# microcontrollerOptical.net
KiCad netlist of a schematic drawn in Altium Designer
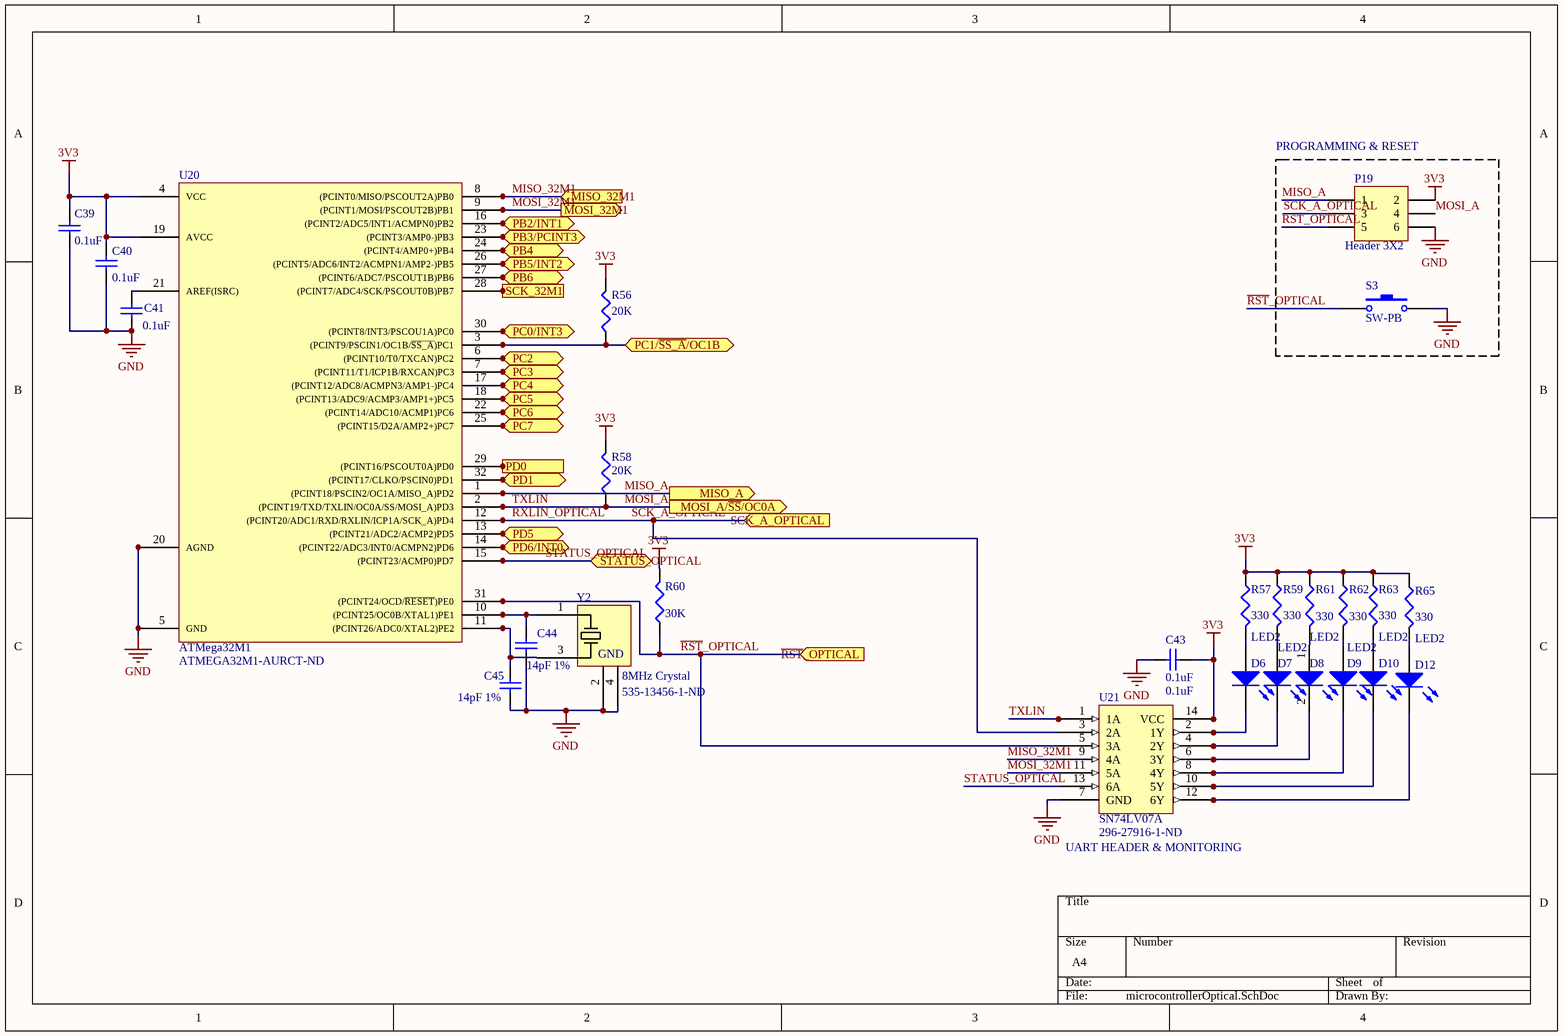
[diagram p0: microcontrollerOptical.SchDoc]

(export (version "E")
  (design (tool "Eeschema 10.0.6"))
  (components
    (comp (ref "C39")
      (value "0.1uF")
      (footprint "1608[0603]")
      (description "Capacitor (Semiconductor SIM Model)")
      (fields (field (name "PUBLISHER") "Altium Limited"))
      (libsource (lib "Miscellaneous Devices") (part "Cap Semi"))
    )
    (comp (ref "C40")
      (value "0.1uF")
      (footprint "1608[0603]")
      (description "Capacitor (Semiconductor SIM Model)")
      (fields (field (name "PUBLISHER") "Altium Limited"))
      (libsource (lib "Miscellaneous Devices") (part "Cap Semi"))
    )
    (comp (ref "C41")
      (value "0.1uF")
      (footprint "1608[0603]")
      (description "Capacitor (Semiconductor SIM Model)")
      (fields (field (name "PUBLISHER") "Altium Limited"))
      (libsource (lib "Miscellaneous Devices") (part "Cap Semi"))
    )
    (comp (ref "C43")
      (value "0.1uF")
      (footprint "1608[0603]")
      (description "Capacitor (Semiconductor SIM Model)")
      (fields (field (name "ALTIUM_VALUE") "0.1uF") (field (name "PUBLISHER") "Altium Limited"))
      (libsource (lib "Miscellaneous Devices") (part "Cap Semi"))
    )
    (comp (ref "C44")
      (value "14pF 1%")
      (footprint "1608[0603]")
      (description "Capacitor (Semiconductor SIM Model)")
      (fields (field (name "Comment") "15pF 1%") (field (name "PUBLISHER") "Altium Limited"))
      (libsource (lib "Miscellaneous Devices") (part "Cap Semi"))
    )
    (comp (ref "C45")
      (value "14pF 1%")
      (footprint "1608[0603]")
      (description "Capacitor (Semiconductor SIM Model)")
      (fields (field (name "Comment") "15pF 1%") (field (name "PUBLISHER") "Altium Limited"))
      (libsource (lib "Miscellaneous Devices") (part "Cap Semi"))
    )
    (comp (ref "D6")
      (value "LED2")
      (footprint "0603-LED")
      (description "Typical RED, GREEN, YELLOW, AMBER GaAs LED")
      (fields (field (name "PUBLISHER") "Altium Limited"))
      (libsource (lib "Miscellaneous Devices") (part "LED2"))
    )
    (comp (ref "D7")
      (value "LED2")
      (footprint "0603-LED")
      (description "Typical RED, GREEN, YELLOW, AMBER GaAs LED")
      (fields (field (name "PUBLISHER") "Altium Limited"))
      (libsource (lib "Miscellaneous Devices") (part "LED2"))
    )
    (comp (ref "D8")
      (value "LED2")
      (footprint "0603-LED")
      (description "Typical RED, GREEN, YELLOW, AMBER GaAs LED")
      (fields (field (name "PUBLISHER") "Altium Limited"))
      (libsource (lib "") (part "LED2_1"))
    )
    (comp (ref "D9")
      (value "LED2")
      (footprint "0603-LED")
      (description "Typical RED, GREEN, YELLOW, AMBER GaAs LED")
      (fields (field (name "PUBLISHER") "Altium Limited"))
      (libsource (lib "Miscellaneous Devices") (part "LED2"))
    )
    (comp (ref "D10")
      (value "LED2")
      (footprint "0603-LED")
      (description "Typical RED, GREEN, YELLOW, AMBER GaAs LED")
      (fields (field (name "PUBLISHER") "Altium Limited"))
      (libsource (lib "Miscellaneous Devices") (part "LED2"))
    )
    (comp (ref "D12")
      (value "LED2")
      (footprint "0603-LED")
      (description "Typical RED, GREEN, YELLOW, AMBER GaAs LED")
      (fields (field (name "PUBLISHER") "Altium Limited"))
      (libsource (lib "Miscellaneous Devices") (part "LED2"))
    )
    (comp (ref "P19")
      (value "Header 3X2")
      (footprint "HDR2X3")
      (description "Header, 3-Pin, Dual row")
      (fields (field (name "PUBLISHER") "Altium Limited"))
      (libsource (lib "Miscellaneous Connectors") (part "Header 3X2"))
    )
    (comp (ref "R56")
      (value "20K")
      (footprint "J1-0603")
      (description "Resistor")
      (fields (field (name "PUBLISHER") "Altium Limited"))
      (libsource (lib "Miscellaneous Devices") (part "Res3"))
    )
    (comp (ref "R57")
      (value "330")
      (footprint "J1-0603")
      (description "Resistor")
      (fields (field (name "PUBLISHER") "Altium Limited"))
      (libsource (lib "Miscellaneous Devices") (part "Res3"))
    )
    (comp (ref "R58")
      (value "20K")
      (footprint "J1-0603")
      (description "Resistor")
      (fields (field (name "PUBLISHER") "Altium Limited"))
      (libsource (lib "Miscellaneous Devices") (part "Res3"))
    )
    (comp (ref "R59")
      (value "330")
      (footprint "J1-0603")
      (description "Resistor")
      (fields (field (name "PUBLISHER") "Altium Limited"))
      (libsource (lib "Miscellaneous Devices") (part "Res3"))
    )
    (comp (ref "R60")
      (value "30K")
      (footprint "J1-0603")
      (description "Resistor")
      (fields (field (name "PUBLISHER") "Altium Limited"))
      (libsource (lib "Miscellaneous Devices") (part "Res3"))
    )
    (comp (ref "R61")
      (value "330")
      (footprint "J1-0603")
      (description "Resistor")
      (fields (field (name "PUBLISHER") "Altium Limited"))
      (libsource (lib "Miscellaneous Devices") (part "Res3"))
    )
    (comp (ref "R62")
      (value "330")
      (footprint "J1-0603")
      (description "Resistor")
      (fields (field (name "PUBLISHER") "Altium Limited"))
      (libsource (lib "Miscellaneous Devices") (part "Res3"))
    )
    (comp (ref "R63")
      (value "330")
      (footprint "J1-0603")
      (description "Resistor")
      (fields (field (name "PUBLISHER") "Altium Limited"))
      (libsource (lib "Miscellaneous Devices") (part "Res3"))
    )
    (comp (ref "R65")
      (value "330")
      (footprint "J1-0603")
      (description "Resistor")
      (fields (field (name "PUBLISHER") "Altium Limited"))
      (libsource (lib "Miscellaneous Devices") (part "Res3"))
    )
    (comp (ref "S3")
      (value "SW-PB")
      (footprint "Pushbutton")
      (description "Switch")
      (fields (field (name "PUBLISHER") "Altium Limited"))
      (libsource (lib "Miscellaneous Devices") (part "SW-PB"))
    )
    (comp (ref "U20")
      (value "ATMega32M1")
      (footprint "QFP80P900X900X120-32N")
      (description "Atmel 8-bit AVR microcontroller.")
      (fields (field (name "SUPPLIER PART NUMBER 1") "ATMEGA32M1-AURCT-ND"))
      (libsource (lib "ICs") (part "ATMega32M1"))
    )
    (comp (ref "U21")
      (value "SN74LV07A")
      (footprint "SOP65P640X120-14N")
      (description "Six element 1-bit non-inverting open-drain buffer.")
      (fields (field (name "SUPPLIER PART NUMBER") "296-27916-1-ND"))
      (libsource (lib "ICs") (part "SN74LV07A"))
    )
    (comp (ref "Y2")
      (value "8MHz Crystal")
      (footprint "OSCSC500X320X110-4N")
      (description "8MHz Abracom 4-pin crystal.")
      (fields (field (name "SUPPLIER PART NUMBER 1") "535-13456-1-ND"))
      (libsource (lib "ICs") (part "8MHz Abracom 4-Pin Crystal"))
    )
  )
  (nets
    (net (code "1") (name "/MISO_32M1") (class "Default")
      (node (ref "U20") (pin "8") (pinfunction "(PCINT0/MISO/PSCOUT2A)PB0_8") (pintype "passive"))
      (node (ref "U21") (pin "9") (pinfunction "4A_9") (pintype "input"))
    )
    (net (code "2") (name "/MISO_A") (class "Default")
      (node (ref "P19") (pin "1") (pinfunction "1_1") (pintype "passive"))
      (node (ref "U20") (pin "1") (pinfunction "(PCINT18/PSCIN2/OC1A/MISO_A)PD2_1") (pintype "passive"))
    )
    (net (code "3") (name "/MOSI_32M1") (class "Default")
      (node (ref "U20") (pin "9") (pinfunction "(PCINT1/MOSI/PSCOUT2B)PB1_9") (pintype "passive"))
      (node (ref "U21") (pin "11") (pinfunction "5A_11") (pintype "input"))
    )
    (net (code "4") (name "/MOSI_A") (class "Default")
      (node (ref "P19") (pin "4") (pinfunction "4_4") (pintype "passive"))
      (node (ref "R58") (pin "1") (pinfunction "1_1") (pintype "passive"))
      (node (ref "U20") (pin "2") (pinfunction "(PCINT19/TXD/TXLIN/OC0A/SS/MOSI_A)PD3_2") (pintype "passive"))
      (node (ref "U21") (pin "1") (pinfunction "1A_1") (pintype "input"))
    )
    (net (code "5") (name "/PB2{slash}INT1") (class "Default")
      (node (ref "U20") (pin "16") (pinfunction "(PCINT2/ADC5/INT1/ACMPN0)PB2_16") (pintype "passive"))
    )
    (net (code "6") (name "/PB3{slash}PCINT3") (class "Default")
      (node (ref "U20") (pin "23") (pinfunction "(PCINT3/AMP0-)PB3_23") (pintype "passive"))
    )
    (net (code "7") (name "/PB4") (class "Default")
      (node (ref "U20") (pin "24") (pinfunction "(PCINT4/AMP0+)PB4_24") (pintype "passive"))
    )
    (net (code "8") (name "/PB5{slash}INT2") (class "Default")
      (node (ref "U20") (pin "26") (pinfunction "(PCINT5/ADC6/INT2/ACMPN1/AMP2-)PB5_26") (pintype "passive"))
    )
    (net (code "9") (name "/PB6") (class "Default")
      (node (ref "U20") (pin "27") (pinfunction "(PCINT6/ADC7/PSCOUT1B)PB6_27") (pintype "passive"))
    )
    (net (code "10") (name "/PC0{slash}INT3") (class "Default")
      (node (ref "U20") (pin "30") (pinfunction "(PCINT8/INT3/PSCOU1A)PC0_30") (pintype "passive"))
    )
    (net (code "11") (name "/PC1{slash}~{SS_A}{slash}OC1B") (class "Default")
      (node (ref "R56") (pin "1") (pinfunction "1_1") (pintype "passive"))
      (node (ref "U20") (pin "3") (pinfunction "(PCINT9/PSCIN1/OC1B/~{SS_A})PC1_3") (pintype "passive"))
    )
    (net (code "12") (name "/PC2") (class "Default")
      (node (ref "U20") (pin "6") (pinfunction "(PCINT10/T0/TXCAN)PC2_6") (pintype "passive"))
    )
    (net (code "13") (name "/PC3") (class "Default")
      (node (ref "U20") (pin "7") (pinfunction "(PCINT11/T1/ICP1B/RXCAN)PC3_7") (pintype "passive"))
    )
    (net (code "14") (name "/PC4") (class "Default")
      (node (ref "U20") (pin "17") (pinfunction "(PCINT12/ADC8/ACMPN3/AMP1-)PC4_17") (pintype "passive"))
    )
    (net (code "15") (name "/PC5") (class "Default")
      (node (ref "U20") (pin "18") (pinfunction "(PCINT13/ADC9/ACMP3/AMP1+)PC5_18") (pintype "passive"))
    )
    (net (code "16") (name "/PC6") (class "Default")
      (node (ref "U20") (pin "22") (pinfunction "(PCINT14/ADC10/ACMP1)PC6_22") (pintype "passive"))
    )
    (net (code "17") (name "/PC7") (class "Default")
      (node (ref "U20") (pin "25") (pinfunction "(PCINT15/D2A/AMP2+)PC7_25") (pintype "passive"))
    )
    (net (code "18") (name "/PD0") (class "Default")
      (node (ref "U20") (pin "29") (pinfunction "(PCINT16/PSCOUT0A)PD0_29") (pintype "passive"))
    )
    (net (code "19") (name "/PD1") (class "Default")
      (node (ref "U20") (pin "32") (pinfunction "(PCINT17/CLKO/PSCIN0)PD1_32") (pintype "passive"))
    )
    (net (code "20") (name "/PD5") (class "Default")
      (node (ref "U20") (pin "13") (pinfunction "(PCINT21/ADC2/ACMP2)PD5_13") (pintype "passive"))
    )
    (net (code "21") (name "/PD6{slash}INT0") (class "Default")
      (node (ref "U20") (pin "14") (pinfunction "(PCINT22/ADC3/INT0/ACMPN2)PD6_14") (pintype "passive"))
    )
    (net (code "22") (name "/RXLIN_OPTICAL") (class "Default")
      (node (ref "P19") (pin "3") (pinfunction "3_3") (pintype "passive"))
      (node (ref "U20") (pin "12") (pinfunction "(PCINT20/ADC1/RXD/RXLIN/ICP1A/SCK_A)PD4_12") (pintype "passive"))
      (node (ref "U21") (pin "3") (pinfunction "2A_3") (pintype "input"))
    )
    (net (code "23") (name "/SCK_32M1") (class "Default")
      (node (ref "U20") (pin "28") (pinfunction "(PCINT7/ADC4/SCK/PSCOUT0B)PB7_28") (pintype "passive"))
    )
    (net (code "24") (name "/STATUS_OPTICAL") (class "Default")
      (node (ref "U20") (pin "15") (pinfunction "(PCINT23/ACMP0)PD7_15") (pintype "passive"))
      (node (ref "U21") (pin "13") (pinfunction "6A_13") (pintype "input"))
    )
    (net (code "25") (name "/~{RST}_OPTICAL") (class "Default")
      (node (ref "P19") (pin "5") (pinfunction "5_5") (pintype "passive"))
      (node (ref "R60") (pin "1") (pinfunction "1_1") (pintype "passive"))
      (node (ref "S3") (pin "1") (pinfunction "1_1") (pintype "passive"))
      (node (ref "U20") (pin "31") (pinfunction "(PCINT24/OCD/~{RESET})PE0_31") (pintype "passive"))
      (node (ref "U21") (pin "5") (pinfunction "3A_5") (pintype "input"))
    )
    (net (code "26") (name "3V3") (class "Default")
      (node (ref "C39") (pin "2") (pinfunction "2_2") (pintype "passive"))
      (node (ref "C40") (pin "2") (pinfunction "2_2") (pintype "passive"))
      (node (ref "C43") (pin "2") (pinfunction "2_2") (pintype "passive"))
      (node (ref "P19") (pin "2") (pinfunction "2_2") (pintype "passive"))
      (node (ref "R56") (pin "2") (pinfunction "2_2") (pintype "passive"))
      (node (ref "R57") (pin "1") (pinfunction "1_1") (pintype "passive"))
      (node (ref "R58") (pin "2") (pinfunction "2_2") (pintype "passive"))
      (node (ref "R59") (pin "1") (pinfunction "1_1") (pintype "passive"))
      (node (ref "R60") (pin "2") (pinfunction "2_2") (pintype "passive"))
      (node (ref "R61") (pin "1") (pinfunction "1_1") (pintype "passive"))
      (node (ref "R62") (pin "1") (pinfunction "1_1") (pintype "passive"))
      (node (ref "R63") (pin "1") (pinfunction "1_1") (pintype "passive"))
      (node (ref "R65") (pin "1") (pinfunction "1_1") (pintype "passive"))
      (node (ref "U20") (pin "19") (pinfunction "AVCC_19") (pintype "passive"))
      (node (ref "U20") (pin "4") (pinfunction "VCC_4") (pintype "passive"))
      (node (ref "U21") (pin "14") (pinfunction "VCC_14") (pintype "power_in"))
    )
    (net (code "27") (name "GND") (class "Default")
      (node (ref "C39") (pin "1") (pinfunction "1_1") (pintype "passive"))
      (node (ref "C40") (pin "1") (pinfunction "1_1") (pintype "passive"))
      (node (ref "C41") (pin "2") (pinfunction "2_2") (pintype "passive"))
      (node (ref "C43") (pin "1") (pinfunction "1_1") (pintype "passive"))
      (node (ref "C44") (pin "1") (pinfunction "1_1") (pintype "passive"))
      (node (ref "C45") (pin "1") (pinfunction "1_1") (pintype "passive"))
      (node (ref "P19") (pin "6") (pinfunction "6_6") (pintype "passive"))
      (node (ref "S3") (pin "2") (pinfunction "2_2") (pintype "passive"))
      (node (ref "U20") (pin "20") (pinfunction "AGND_20") (pintype "passive"))
      (node (ref "U20") (pin "5") (pinfunction "GND_5") (pintype "passive"))
      (node (ref "U21") (pin "7") (pinfunction "GND_7") (pintype "power_in"))
      (node (ref "Y2") (pin "2") (pinfunction "5_2") (pintype "passive"))
      (node (ref "Y2") (pin "4") (pinfunction "4_4") (pintype "passive"))
    )
    (net (code "28") (name "Net-(D6-A)") (class "Default")
      (node (ref "D6") (pin "1") (pinfunction "A_1") (pintype "passive"))
      (node (ref "R57") (pin "2") (pinfunction "2_2") (pintype "passive"))
    )
    (net (code "29") (name "Net-(D6-K)") (class "Default")
      (node (ref "D6") (pin "2") (pinfunction "K_2") (pintype "passive"))
      (node (ref "U21") (pin "2") (pinfunction "1Y_2") (pintype "output"))
    )
    (net (code "30") (name "Net-(D7-A)") (class "Default")
      (node (ref "D7") (pin "1") (pinfunction "A_1") (pintype "passive"))
      (node (ref "R59") (pin "2") (pinfunction "2_2") (pintype "passive"))
    )
    (net (code "31") (name "Net-(D7-K)") (class "Default")
      (node (ref "D7") (pin "2") (pinfunction "K_2") (pintype "passive"))
      (node (ref "U21") (pin "4") (pinfunction "2Y_4") (pintype "output"))
    )
    (net (code "32") (name "Net-(D8-A)") (class "Default")
      (node (ref "D8") (pin "1") (pinfunction "A_1") (pintype "passive"))
      (node (ref "R61") (pin "2") (pinfunction "2_2") (pintype "passive"))
    )
    (net (code "33") (name "Net-(D8-K)") (class "Default")
      (node (ref "D8") (pin "2") (pinfunction "K_2") (pintype "passive"))
      (node (ref "U21") (pin "6") (pinfunction "3Y_6") (pintype "output"))
    )
    (net (code "34") (name "Net-(D9-A)") (class "Default")
      (node (ref "D9") (pin "1") (pinfunction "A_1") (pintype "passive"))
      (node (ref "R62") (pin "2") (pinfunction "2_2") (pintype "passive"))
    )
    (net (code "35") (name "Net-(D9-K)") (class "Default")
      (node (ref "D9") (pin "2") (pinfunction "K_2") (pintype "passive"))
      (node (ref "U21") (pin "8") (pinfunction "4Y_8") (pintype "output"))
    )
    (net (code "36") (name "Net-(D10-A)") (class "Default")
      (node (ref "D10") (pin "1") (pinfunction "A_1") (pintype "passive"))
      (node (ref "R63") (pin "2") (pinfunction "2_2") (pintype "passive"))
    )
    (net (code "37") (name "Net-(D10-K)") (class "Default")
      (node (ref "D10") (pin "2") (pinfunction "K_2") (pintype "passive"))
      (node (ref "U21") (pin "10") (pinfunction "5Y_10") (pintype "output"))
    )
    (net (code "38") (name "Net-(D12-A)") (class "Default")
      (node (ref "D12") (pin "1") (pinfunction "A_1") (pintype "passive"))
      (node (ref "R65") (pin "2") (pinfunction "2_2") (pintype "passive"))
    )
    (net (code "39") (name "Net-(D12-K)") (class "Default")
      (node (ref "D12") (pin "2") (pinfunction "K_2") (pintype "passive"))
      (node (ref "U21") (pin "12") (pinfunction "6Y_12") (pintype "output"))
    )
    (net (code "40") (name "Net-(U20-(PCINT25{slash}OC0B{slash}XTAL1)PE1)") (class "Default")
      (node (ref "C44") (pin "2") (pinfunction "2_2") (pintype "passive"))
      (node (ref "U20") (pin "10") (pinfunction "(PCINT25/OC0B/XTAL1)PE1_10") (pintype "passive"))
      (node (ref "Y2") (pin "1") (pinfunction "IN_1") (pintype "passive"))
    )
    (net (code "41") (name "Net-(U20-(PCINT26{slash}ADC0{slash}XTAL2)PE2)") (class "Default")
      (node (ref "C45") (pin "2") (pinfunction "2_2") (pintype "passive"))
      (node (ref "U20") (pin "11") (pinfunction "(PCINT26/ADC0/XTAL2)PE2_11") (pintype "passive"))
      (node (ref "Y2") (pin "3") (pinfunction "IN_3") (pintype "passive"))
    )
    (net (code "42") (name "Net-(U20-AREF(ISRC))") (class "Default")
      (node (ref "C41") (pin "1") (pinfunction "1_1") (pintype "passive"))
      (node (ref "U20") (pin "21") (pinfunction "AREF(ISRC)_21") (pintype "passive"))
    )
  )
)
